# relay_dip_v03.net
KiCad netlist of a schematic drawn in EAGLE
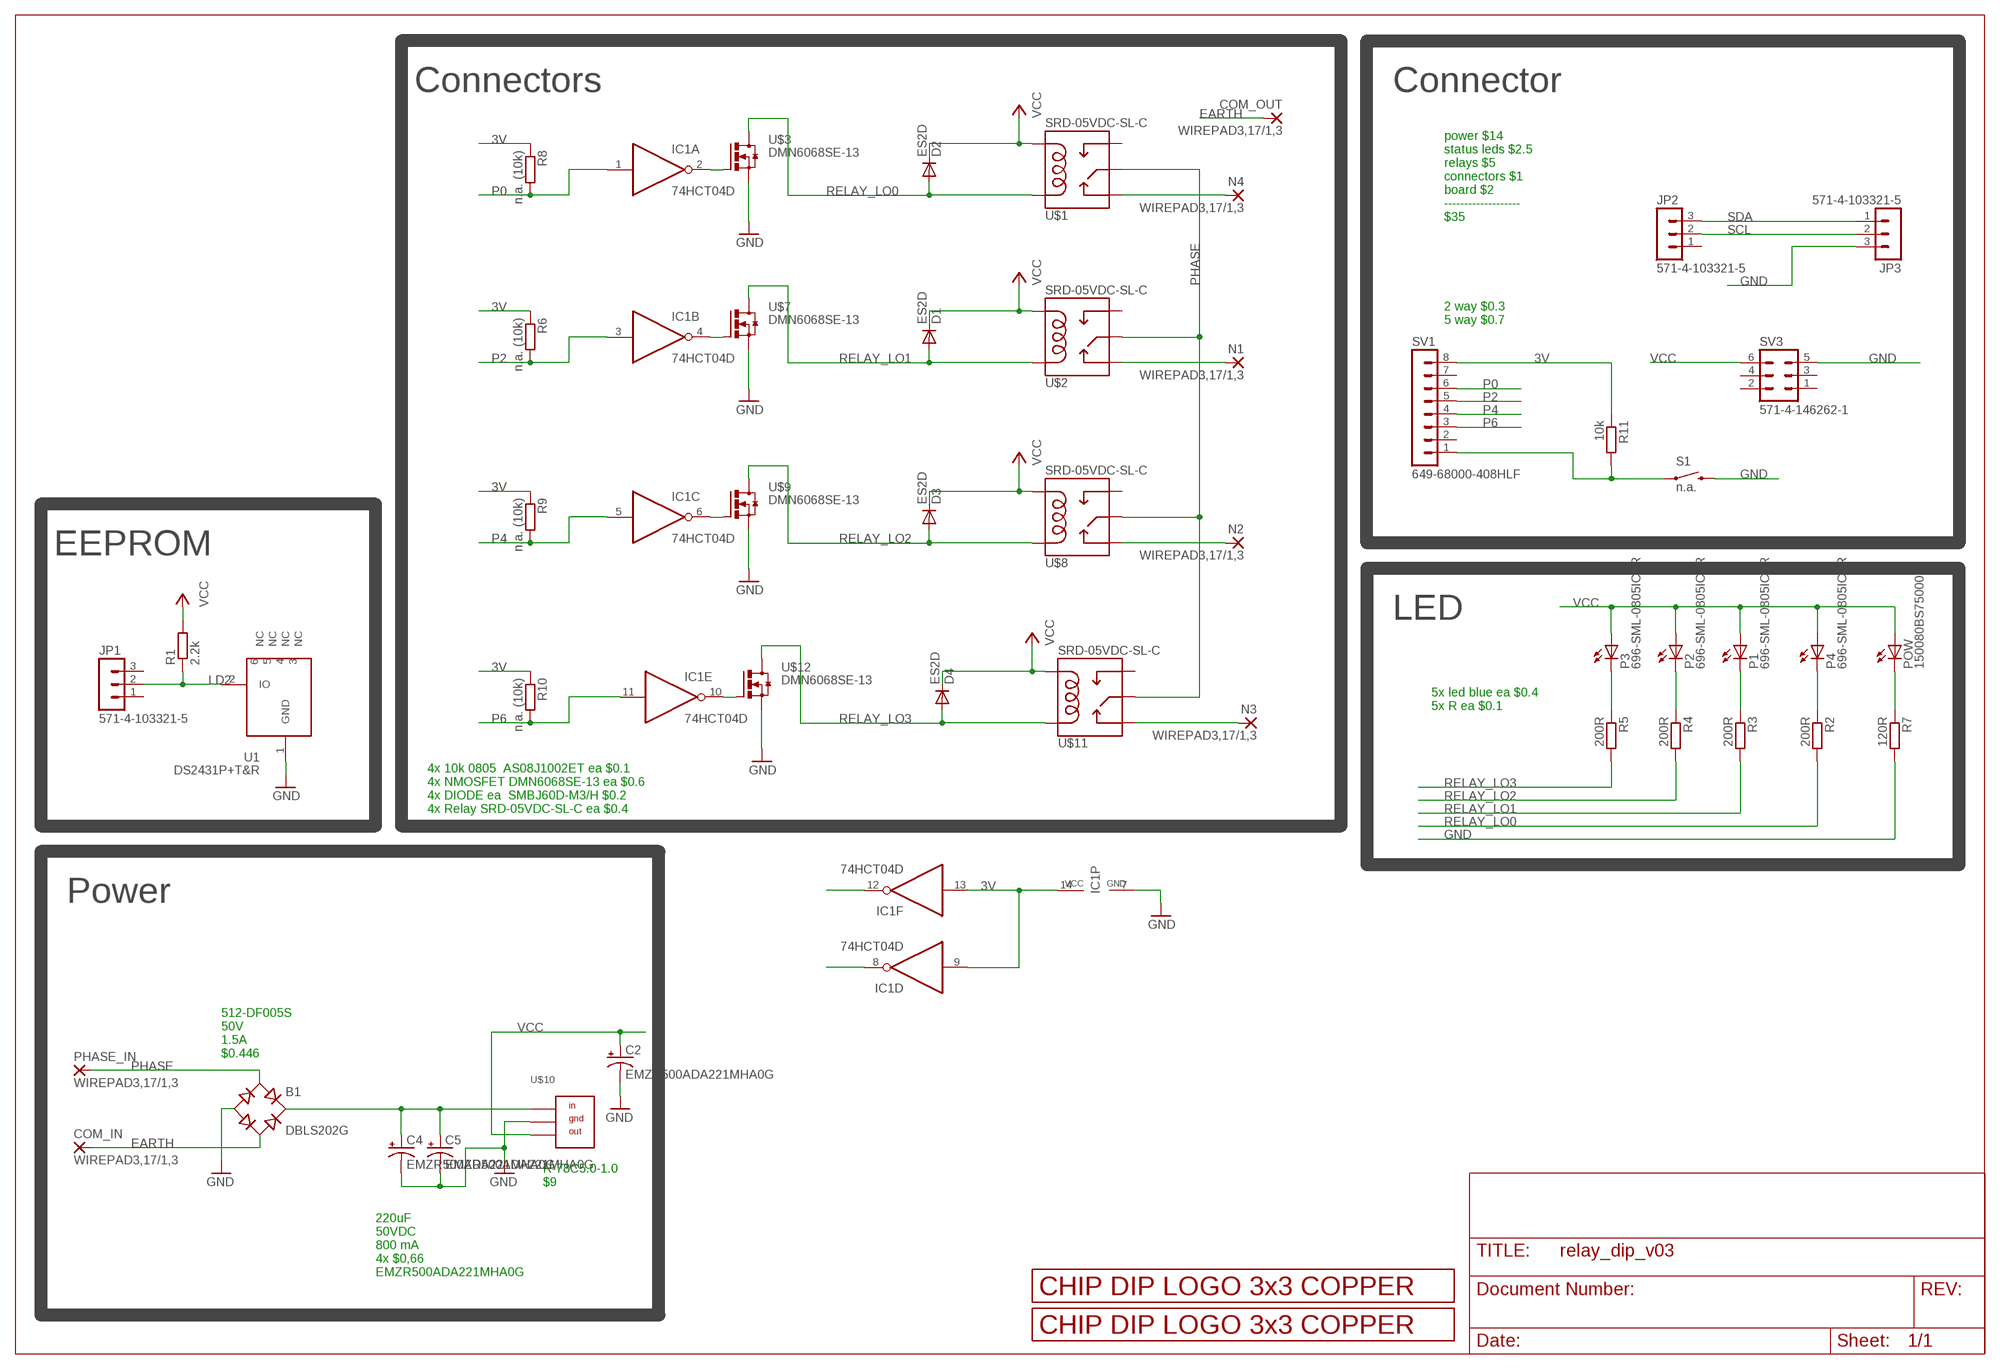
[diagram p0: schematic, sheet 1]

(export (version "E")
  (design (tool "Eeschema 10.0.6"))
  (components
    (comp (ref "B1")
      (value "DBLS202G")
      (footprint "eagle-import:DBS")
      (libsource (lib "eagle-import") (part "DB?GLS202"))
    )
    (comp (ref "C2")
      (value "EMZR500ADA221MHA0G")
      (footprint "eagle-import:150CLZ-0810")
      (libsource (lib "eagle-import") (part "CPOL-US150CLZ-0810"))
    )
    (comp (ref "C4")
      (value "EMZR500ADA221MHA0G")
      (footprint "eagle-import:150CLZ-0810")
      (libsource (lib "eagle-import") (part "CPOL-US150CLZ-0810"))
    )
    (comp (ref "C5")
      (value "EMZR500ADA221MHA0G")
      (footprint "eagle-import:150CLZ-0810")
      (libsource (lib "eagle-import") (part "CPOL-US150CLZ-0810"))
    )
    (comp (ref "COM_IN")
      (value "WIREPAD3,17/1,3")
      (footprint "eagle-import:3,17_1,3")
      (libsource (lib "eagle-import") (part "WIREPAD3,17/1,3"))
    )
    (comp (ref "COM_OUT")
      (value "WIREPAD3,17/1,3")
      (footprint "eagle-import:3,17_1,3")
      (libsource (lib "eagle-import") (part "WIREPAD3,17/1,3"))
    )
    (comp (ref "D1")
      (value "ES2D")
      (footprint "eagle-import:SMB")
      (libsource (lib "eagle-import") (part "DIODE-SMB"))
    )
    (comp (ref "D2")
      (value "ES2D")
      (footprint "eagle-import:SMB")
      (libsource (lib "eagle-import") (part "DIODE-SMB"))
    )
    (comp (ref "D3")
      (value "ES2D")
      (footprint "eagle-import:SMB")
      (libsource (lib "eagle-import") (part "DIODE-SMB"))
    )
    (comp (ref "D4")
      (value "ES2D")
      (footprint "eagle-import:SMB")
      (libsource (lib "eagle-import") (part "DIODE-SMB"))
    )
    (comp (ref "IC1")
      (value "74HCT04D")
      (footprint "eagle-import:SO14")
      (libsource (lib "eagle-import") (part "7404DHCT"))
    )
    (comp (ref "JP1")
      (value "571-4-103321-5")
      (footprint "eagle-import:MA03-1")
      (libsource (lib "eagle-import") (part "MA03-1"))
    )
    (comp (ref "JP2")
      (value "571-4-103321-5")
      (footprint "eagle-import:MA03-1")
      (libsource (lib "eagle-import") (part "MA03-1"))
    )
    (comp (ref "JP3")
      (value "571-4-103321-5")
      (footprint "eagle-import:MA03-1")
      (libsource (lib "eagle-import") (part "MA03-1"))
    )
    (comp (ref "N1")
      (value "WIREPAD3,17/1,3")
      (footprint "eagle-import:3,17_1,3")
      (libsource (lib "eagle-import") (part "WIREPAD3,17/1,3"))
    )
    (comp (ref "N2")
      (value "WIREPAD3,17/1,3")
      (footprint "eagle-import:3,17_1,3")
      (libsource (lib "eagle-import") (part "WIREPAD3,17/1,3"))
    )
    (comp (ref "N3")
      (value "WIREPAD3,17/1,3")
      (footprint "eagle-import:3,17_1,3")
      (libsource (lib "eagle-import") (part "WIREPAD3,17/1,3"))
    )
    (comp (ref "N4")
      (value "WIREPAD3,17/1,3")
      (footprint "eagle-import:3,17_1,3")
      (libsource (lib "eagle-import") (part "WIREPAD3,17/1,3"))
    )
    (comp (ref "P1")
      (value "696-SML-0805ICTR")
      (footprint "eagle-import:CHIP-LED0805")
      (libsource (lib "eagle-import") (part "LEDCHIP-LED0805"))
    )
    (comp (ref "P2")
      (value "696-SML-0805ICTR")
      (footprint "eagle-import:CHIP-LED0805")
      (libsource (lib "eagle-import") (part "LEDCHIP-LED0805"))
    )
    (comp (ref "P3")
      (value "696-SML-0805ICTR")
      (footprint "eagle-import:CHIP-LED0805")
      (libsource (lib "eagle-import") (part "LEDCHIP-LED0805"))
    )
    (comp (ref "P4")
      (value "696-SML-0805ICTR")
      (footprint "eagle-import:CHIP-LED0805")
      (libsource (lib "eagle-import") (part "LEDCHIP-LED0805"))
    )
    (comp (ref "PHASE_IN")
      (value "WIREPAD3,17/1,3")
      (footprint "eagle-import:3,17_1,3")
      (libsource (lib "eagle-import") (part "WIREPAD3,17/1,3"))
    )
    (comp (ref "POW")
      (value "150080BS75000")
      (footprint "eagle-import:CHIP-LED0805")
      (libsource (lib "eagle-import") (part "LEDCHIP-LED0805"))
    )
    (comp (ref "R1")
      (value "2.2k")
      (footprint "eagle-import:R0805")
      (libsource (lib "eagle-import") (part "R-EU_R0805"))
    )
    (comp (ref "R2")
      (value "200R")
      (footprint "eagle-import:R0805")
      (libsource (lib "eagle-import") (part "R-EU_R0805"))
    )
    (comp (ref "R3")
      (value "200R")
      (footprint "eagle-import:R0805")
      (libsource (lib "eagle-import") (part "R-EU_R0805"))
    )
    (comp (ref "R4")
      (value "200R")
      (footprint "eagle-import:R0805")
      (libsource (lib "eagle-import") (part "R-EU_R0805"))
    )
    (comp (ref "R5")
      (value "200R")
      (footprint "eagle-import:R0805")
      (libsource (lib "eagle-import") (part "R-EU_R0805"))
    )
    (comp (ref "R6")
      (value "n.a. (10k)")
      (footprint "eagle-import:R0805")
      (libsource (lib "eagle-import") (part "R-EU_R0805"))
    )
    (comp (ref "R7")
      (value "120R")
      (footprint "eagle-import:R0805")
      (libsource (lib "eagle-import") (part "R-EU_R0805"))
    )
    (comp (ref "R8")
      (value "n.a. (10k)")
      (footprint "eagle-import:R0805")
      (libsource (lib "eagle-import") (part "R-EU_R0805"))
    )
    (comp (ref "R9")
      (value "n.a. (10k)")
      (footprint "eagle-import:R0805")
      (libsource (lib "eagle-import") (part "R-EU_R0805"))
    )
    (comp (ref "R10")
      (value "n.a. (10k)")
      (footprint "eagle-import:R0805")
      (libsource (lib "eagle-import") (part "R-EU_R0805"))
    )
    (comp (ref "R11")
      (value "10k")
      (footprint "eagle-import:R0805")
      (libsource (lib "eagle-import") (part "R-EU_R0805"))
    )
    (comp (ref "S1")
      (value "n.a.")
      (footprint "eagle-import:TACTILE-SWITCH-SMD")
      (libsource (lib "eagle-import") (part "SWITCH-MOMENTARY-2SMD"))
    )
    (comp (ref "SV1")
      (value "649-68000-408HLF")
      (footprint "eagle-import:MA08-1")
      (libsource (lib "eagle-import") (part "MA08-1"))
    )
    (comp (ref "SV3")
      (value "571-4-146262-1")
      (footprint "eagle-import:MA03-2")
      (libsource (lib "eagle-import") (part "MA03-2"))
    )
    (comp (ref "U$1")
      (value "SRD-05VDC-SL-C")
      (footprint "eagle-import:SRD-05VDC-SL-C")
      (libsource (lib "eagle-import") (part "RELAYPTH"))
    )
    (comp (ref "U$2")
      (value "SRD-05VDC-SL-C")
      (footprint "eagle-import:SRD-05VDC-SL-C")
      (libsource (lib "eagle-import") (part "RELAYPTH"))
    )
    (comp (ref "U$3")
      (value "DMN6068SE-13")
      (footprint "eagle-import:SOT223")
      (libsource (lib "eagle-import") (part "NMOSFET_SMD_223"))
    )
    (comp (ref "U$4")
      (value "LOGO_3X3_COPPER")
      (footprint "eagle-import:LOGO_3X3_COPPER")
      (libsource (lib "eagle-import") (part "LOGO_3X3_COPPER"))
    )
    (comp (ref "U$6")
      (value "LOGO_3X3_COPPER")
      (footprint "eagle-import:LOGO_3X3_COPPER")
      (libsource (lib "eagle-import") (part "LOGO_3X3_COPPER"))
    )
    (comp (ref "U$7")
      (value "DMN6068SE-13")
      (footprint "eagle-import:SOT223")
      (libsource (lib "eagle-import") (part "NMOSFET_SMD_223"))
    )
    (comp (ref "U$8")
      (value "SRD-05VDC-SL-C")
      (footprint "eagle-import:SRD-05VDC-SL-C")
      (libsource (lib "eagle-import") (part "RELAYPTH"))
    )
    (comp (ref "U$9")
      (value "DMN6068SE-13")
      (footprint "eagle-import:SOT223")
      (libsource (lib "eagle-import") (part "NMOSFET_SMD_223"))
    )
    (comp (ref "U$10")
      (value "R-7805-1.0")
      (footprint "eagle-import:SIP3")
      (libsource (lib "eagle-import") (part "R-7805-1.0"))
    )
    (comp (ref "U$11")
      (value "SRD-05VDC-SL-C")
      (footprint "eagle-import:SRD-05VDC-SL-C")
      (libsource (lib "eagle-import") (part "RELAYPTH"))
    )
    (comp (ref "U$12")
      (value "DMN6068SE-13")
      (footprint "eagle-import:SOT223")
      (libsource (lib "eagle-import") (part "NMOSFET_SMD_223"))
    )
    (comp (ref "U1")
      (value "DS2431P+T&R")
      (footprint "eagle-import:TSOC6")
      (fields (field (name "MFG") "DIGIKEY"))
      (libsource (lib "eagle-import") (part "DS2431P"))
    )
  )
  (nets
    (net (code "1") (name "/3V") (class "Default")
      (node (ref "IC1") (pin "13") (pinfunction "I_13") (pintype "input"))
      (node (ref "IC1") (pin "14") (pinfunction "VCC_14") (pintype "power_in"))
      (node (ref "IC1") (pin "9") (pinfunction "I_9") (pintype "input"))
      (node (ref "R10") (pin "1") (pinfunction "1_1") (pintype "passive"))
      (node (ref "R11") (pin "1") (pinfunction "1_1") (pintype "passive"))
      (node (ref "R6") (pin "1") (pinfunction "1_1") (pintype "passive"))
      (node (ref "R8") (pin "1") (pinfunction "1_1") (pintype "passive"))
      (node (ref "R9") (pin "1") (pinfunction "1_1") (pintype "passive"))
      (node (ref "SV1") (pin "8") (pinfunction "8_8") (pintype "passive"))
    )
    (net (code "2") (name "/EARTH") (class "Default")
      (node (ref "B1") (pin "AC2") (pinfunction "AC2_AC2") (pintype "passive"))
      (node (ref "COM_IN") (pin "1") (pinfunction "P_1") (pintype "passive"))
      (node (ref "COM_OUT") (pin "1") (pinfunction "P_1") (pintype "passive"))
    )
    (net (code "3") (name "/LD2") (class "Default")
      (node (ref "JP1") (pin "2") (pinfunction "2_2") (pintype "passive"))
      (node (ref "R1") (pin "1") (pinfunction "1_1") (pintype "passive"))
      (node (ref "U1") (pin "2") (pinfunction "IO_2") (pintype "bidirectional"))
    )
    (net (code "4") (name "/P0") (class "Default")
      (node (ref "IC1") (pin "1") (pinfunction "I_1") (pintype "input"))
      (node (ref "R8") (pin "2") (pinfunction "2_2") (pintype "passive"))
      (node (ref "SV1") (pin "6") (pinfunction "6_6") (pintype "passive"))
    )
    (net (code "5") (name "/P2") (class "Default")
      (node (ref "IC1") (pin "3") (pinfunction "I_3") (pintype "input"))
      (node (ref "R6") (pin "2") (pinfunction "2_2") (pintype "passive"))
      (node (ref "SV1") (pin "5") (pinfunction "5_5") (pintype "passive"))
    )
    (net (code "6") (name "/P4") (class "Default")
      (node (ref "IC1") (pin "5") (pinfunction "I_5") (pintype "input"))
      (node (ref "R9") (pin "2") (pinfunction "2_2") (pintype "passive"))
      (node (ref "SV1") (pin "4") (pinfunction "4_4") (pintype "passive"))
    )
    (net (code "7") (name "/P6") (class "Default")
      (node (ref "IC1") (pin "11") (pinfunction "I_11") (pintype "input"))
      (node (ref "R10") (pin "2") (pinfunction "2_2") (pintype "passive"))
      (node (ref "SV1") (pin "3") (pinfunction "3_3") (pintype "passive"))
    )
    (net (code "8") (name "/PHASE") (class "Default")
      (node (ref "B1") (pin "AC1") (pinfunction "AC1_AC1") (pintype "passive"))
      (node (ref "PHASE_IN") (pin "1") (pinfunction "P_1") (pintype "passive"))
      (node (ref "U$1") (pin "SWCOMMON") (pinfunction "SWCOMMON_SWCOMMON") (pintype "bidirectional"))
      (node (ref "U$11") (pin "SWCOMMON") (pinfunction "SWCOMMON_SWCOMMON") (pintype "bidirectional"))
      (node (ref "U$2") (pin "SWCOMMON") (pinfunction "SWCOMMON_SWCOMMON") (pintype "bidirectional"))
      (node (ref "U$8") (pin "SWCOMMON") (pinfunction "SWCOMMON_SWCOMMON") (pintype "bidirectional"))
    )
    (net (code "9") (name "/RELAY_LO0") (class "Default")
      (node (ref "D2") (pin "A") (pinfunction "A_A") (pintype "passive"))
      (node (ref "R2") (pin "2") (pinfunction "2_2") (pintype "passive"))
      (node (ref "U$1") (pin "COIL1") (pinfunction "COIL1_COIL1") (pintype "bidirectional"))
      (node (ref "U$3") (pin "2") (pinfunction "D_2") (pintype "passive"))
      (node (ref "U$3") (pin "4") (pinfunction "D_4") (pintype "passive"))
    )
    (net (code "10") (name "/RELAY_LO1") (class "Default")
      (node (ref "D1") (pin "A") (pinfunction "A_A") (pintype "passive"))
      (node (ref "R3") (pin "2") (pinfunction "2_2") (pintype "passive"))
      (node (ref "U$2") (pin "COIL1") (pinfunction "COIL1_COIL1") (pintype "bidirectional"))
      (node (ref "U$7") (pin "2") (pinfunction "D_2") (pintype "passive"))
      (node (ref "U$7") (pin "4") (pinfunction "D_4") (pintype "passive"))
    )
    (net (code "11") (name "/RELAY_LO2") (class "Default")
      (node (ref "D3") (pin "A") (pinfunction "A_A") (pintype "passive"))
      (node (ref "R4") (pin "2") (pinfunction "2_2") (pintype "passive"))
      (node (ref "U$8") (pin "COIL1") (pinfunction "COIL1_COIL1") (pintype "bidirectional"))
      (node (ref "U$9") (pin "2") (pinfunction "D_2") (pintype "passive"))
      (node (ref "U$9") (pin "4") (pinfunction "D_4") (pintype "passive"))
    )
    (net (code "12") (name "/RELAY_LO3") (class "Default")
      (node (ref "D4") (pin "A") (pinfunction "A_A") (pintype "passive"))
      (node (ref "R5") (pin "2") (pinfunction "2_2") (pintype "passive"))
      (node (ref "U$11") (pin "COIL1") (pinfunction "COIL1_COIL1") (pintype "bidirectional"))
      (node (ref "U$12") (pin "2") (pinfunction "D_2") (pintype "passive"))
      (node (ref "U$12") (pin "4") (pinfunction "D_4") (pintype "passive"))
    )
    (net (code "13") (name "/SCL") (class "Default")
      (node (ref "JP2") (pin "2") (pinfunction "2_2") (pintype "passive"))
      (node (ref "JP3") (pin "2") (pinfunction "2_2") (pintype "passive"))
    )
    (net (code "14") (name "/SDA") (class "Default")
      (node (ref "JP2") (pin "3") (pinfunction "3_3") (pintype "passive"))
      (node (ref "JP3") (pin "1") (pinfunction "1_1") (pintype "passive"))
    )
    (net (code "15") (name "GND") (class "Default")
      (node (ref "B1") (pin "-") (pinfunction "-_-") (pintype "passive"))
      (node (ref "C2") (pin "-") (pinfunction "-_-") (pintype "passive"))
      (node (ref "C4") (pin "-") (pinfunction "-_-") (pintype "passive"))
      (node (ref "C5") (pin "-") (pinfunction "-_-") (pintype "passive"))
      (node (ref "IC1") (pin "7") (pinfunction "GND_7") (pintype "power_in"))
      (node (ref "JP3") (pin "3") (pinfunction "3_3") (pintype "passive"))
      (node (ref "R7") (pin "2") (pinfunction "2_2") (pintype "passive"))
      (node (ref "S1") (pin "3") (pinfunction "2_3") (pintype "passive"))
      (node (ref "SV3") (pin "5") (pinfunction "5_5") (pintype "passive"))
      (node (ref "U$10") (pin "GND") (pinfunction "GND_GND") (pintype "bidirectional"))
      (node (ref "U$12") (pin "3") (pinfunction "S_3") (pintype "passive"))
      (node (ref "U$3") (pin "3") (pinfunction "S_3") (pintype "passive"))
      (node (ref "U$7") (pin "3") (pinfunction "S_3") (pintype "passive"))
      (node (ref "U$9") (pin "3") (pinfunction "S_3") (pintype "passive"))
      (node (ref "U1") (pin "1") (pinfunction "GND_1") (pintype "bidirectional"))
    )
    (net (code "16") (name "Net-(B1-Pad+)") (class "Default")
      (node (ref "B1") (pin "+") (pinfunction "+_+") (pintype "passive"))
      (node (ref "C4") (pin "+") (pinfunction "+_+") (pintype "passive"))
      (node (ref "C5") (pin "+") (pinfunction "+_+") (pintype "passive"))
      (node (ref "U$10") (pin "IN") (pinfunction "IN_IN") (pintype "bidirectional"))
    )
    (net (code "17") (name "Net-(IC1A-O)") (class "Default")
      (node (ref "IC1") (pin "2") (pinfunction "O_2") (pintype "output"))
      (node (ref "U$3") (pin "1") (pinfunction "G_1") (pintype "passive"))
    )
    (net (code "18") (name "Net-(IC1B-O)") (class "Default")
      (node (ref "IC1") (pin "4") (pinfunction "O_4") (pintype "output"))
      (node (ref "U$7") (pin "1") (pinfunction "G_1") (pintype "passive"))
    )
    (net (code "19") (name "Net-(IC1C-O)") (class "Default")
      (node (ref "IC1") (pin "6") (pinfunction "O_6") (pintype "output"))
      (node (ref "U$9") (pin "1") (pinfunction "G_1") (pintype "passive"))
    )
    (net (code "20") (name "Net-(IC1E-O)") (class "Default")
      (node (ref "IC1") (pin "10") (pinfunction "O_10") (pintype "output"))
      (node (ref "U$12") (pin "1") (pinfunction "G_1") (pintype "passive"))
    )
    (net (code "21") (name "Net-(N1-P)") (class "Default")
      (node (ref "N1") (pin "1") (pinfunction "P_1") (pintype "passive"))
      (node (ref "U$2") (pin "SWCLOSED") (pinfunction "SWCLOSE_SWCLOSED") (pintype "bidirectional"))
    )
    (net (code "22") (name "Net-(N2-P)") (class "Default")
      (node (ref "N2") (pin "1") (pinfunction "P_1") (pintype "passive"))
      (node (ref "U$8") (pin "SWCLOSED") (pinfunction "SWCLOSE_SWCLOSED") (pintype "bidirectional"))
    )
    (net (code "23") (name "Net-(N3-P)") (class "Default")
      (node (ref "N3") (pin "1") (pinfunction "P_1") (pintype "passive"))
      (node (ref "U$11") (pin "SWCLOSED") (pinfunction "SWCLOSE_SWCLOSED") (pintype "bidirectional"))
    )
    (net (code "24") (name "Net-(N4-P)") (class "Default")
      (node (ref "N4") (pin "1") (pinfunction "P_1") (pintype "passive"))
      (node (ref "U$1") (pin "SWCLOSED") (pinfunction "SWCLOSE_SWCLOSED") (pintype "bidirectional"))
    )
    (net (code "25") (name "Net-(P1-PadC)") (class "Default")
      (node (ref "P1") (pin "C") (pinfunction "C_C") (pintype "passive"))
      (node (ref "R3") (pin "1") (pinfunction "1_1") (pintype "passive"))
    )
    (net (code "26") (name "Net-(P2-PadC)") (class "Default")
      (node (ref "P2") (pin "C") (pinfunction "C_C") (pintype "passive"))
      (node (ref "R4") (pin "1") (pinfunction "1_1") (pintype "passive"))
    )
    (net (code "27") (name "Net-(P3-PadC)") (class "Default")
      (node (ref "P3") (pin "C") (pinfunction "C_C") (pintype "passive"))
      (node (ref "R5") (pin "1") (pinfunction "1_1") (pintype "passive"))
    )
    (net (code "28") (name "Net-(P4-PadC)") (class "Default")
      (node (ref "P4") (pin "C") (pinfunction "C_C") (pintype "passive"))
      (node (ref "R2") (pin "1") (pinfunction "1_1") (pintype "passive"))
    )
    (net (code "29") (name "Net-(POW-PadC)") (class "Default")
      (node (ref "POW") (pin "C") (pinfunction "C_C") (pintype "passive"))
      (node (ref "R7") (pin "1") (pinfunction "1_1") (pintype "passive"))
    )
    (net (code "30") (name "Net-(R11-Pad2)") (class "Default")
      (node (ref "R11") (pin "2") (pinfunction "2_2") (pintype "passive"))
      (node (ref "S1") (pin "1") (pinfunction "1_1") (pintype "passive"))
      (node (ref "SV1") (pin "1") (pinfunction "1_1") (pintype "passive"))
    )
    (net (code "31") (name "VCC") (class "Default")
      (node (ref "C2") (pin "+") (pinfunction "+_+") (pintype "passive"))
      (node (ref "D1") (pin "C") (pinfunction "C_C") (pintype "passive"))
      (node (ref "D2") (pin "C") (pinfunction "C_C") (pintype "passive"))
      (node (ref "D3") (pin "C") (pinfunction "C_C") (pintype "passive"))
      (node (ref "D4") (pin "C") (pinfunction "C_C") (pintype "passive"))
      (node (ref "P1") (pin "A") (pinfunction "A_A") (pintype "passive"))
      (node (ref "P2") (pin "A") (pinfunction "A_A") (pintype "passive"))
      (node (ref "P3") (pin "A") (pinfunction "A_A") (pintype "passive"))
      (node (ref "P4") (pin "A") (pinfunction "A_A") (pintype "passive"))
      (node (ref "POW") (pin "A") (pinfunction "A_A") (pintype "passive"))
      (node (ref "R1") (pin "2") (pinfunction "2_2") (pintype "passive"))
      (node (ref "SV3") (pin "6") (pinfunction "6_6") (pintype "passive"))
      (node (ref "U$1") (pin "COIL0") (pinfunction "COIL0_COIL0") (pintype "bidirectional"))
      (node (ref "U$10") (pin "OUT") (pinfunction "OUT_OUT") (pintype "bidirectional"))
      (node (ref "U$11") (pin "COIL0") (pinfunction "COIL0_COIL0") (pintype "bidirectional"))
      (node (ref "U$2") (pin "COIL0") (pinfunction "COIL0_COIL0") (pintype "bidirectional"))
      (node (ref "U$8") (pin "COIL0") (pinfunction "COIL0_COIL0") (pintype "bidirectional"))
    )
    (net (code "32") (name "unconnected-(IC1D-O-Pad8)") (class "Default")
      (node (ref "IC1") (pin "8") (pinfunction "O_8") (pintype "output"))
    )
    (net (code "33") (name "unconnected-(IC1F-O-Pad12)") (class "Default")
      (node (ref "IC1") (pin "12") (pinfunction "O_12") (pintype "output"))
    )
    (net (code "34") (name "unconnected-(JP1-Pad1)") (class "Default")
      (node (ref "JP1") (pin "1") (pinfunction "1_1") (pintype "passive"))
    )
    (net (code "35") (name "unconnected-(JP1-Pad3)") (class "Default")
      (node (ref "JP1") (pin "3") (pinfunction "3_3") (pintype "passive"))
    )
    (net (code "36") (name "unconnected-(JP2-Pad1)") (class "Default")
      (node (ref "JP2") (pin "1") (pinfunction "1_1") (pintype "passive"))
    )
    (net (code "37") (name "unconnected-(SV1-Pad2)") (class "Default")
      (node (ref "SV1") (pin "2") (pinfunction "2_2") (pintype "passive"))
    )
    (net (code "38") (name "unconnected-(SV1-Pad7)") (class "Default")
      (node (ref "SV1") (pin "7") (pinfunction "7_7") (pintype "passive"))
    )
    (net (code "39") (name "unconnected-(SV3-Pad1)") (class "Default")
      (node (ref "SV3") (pin "1") (pinfunction "1_1") (pintype "passive"))
    )
    (net (code "40") (name "unconnected-(SV3-Pad2)") (class "Default")
      (node (ref "SV3") (pin "2") (pinfunction "2_2") (pintype "passive"))
    )
    (net (code "41") (name "unconnected-(SV3-Pad3)") (class "Default")
      (node (ref "SV3") (pin "3") (pinfunction "3_3") (pintype "passive"))
    )
    (net (code "42") (name "unconnected-(SV3-Pad4)") (class "Default")
      (node (ref "SV3") (pin "4") (pinfunction "4_4") (pintype "passive"))
    )
    (net (code "43") (name "unconnected-(U$1-PadSWOPEN)") (class "Default")
      (node (ref "U$1") (pin "SWOPEN") (pinfunction "SWOPEN_SWOPEN") (pintype "bidirectional"))
    )
    (net (code "44") (name "unconnected-(U$2-PadSWOPEN)") (class "Default")
      (node (ref "U$2") (pin "SWOPEN") (pinfunction "SWOPEN_SWOPEN") (pintype "bidirectional"))
    )
    (net (code "45") (name "unconnected-(U$8-PadSWOPEN)") (class "Default")
      (node (ref "U$8") (pin "SWOPEN") (pinfunction "SWOPEN_SWOPEN") (pintype "bidirectional"))
    )
    (net (code "46") (name "unconnected-(U$11-PadSWOPEN)") (class "Default")
      (node (ref "U$11") (pin "SWOPEN") (pinfunction "SWOPEN_SWOPEN") (pintype "bidirectional"))
    )
    (net (code "47") (name "unconnected-(U1-NC-Pad3)") (class "Default")
      (node (ref "U1") (pin "3") (pinfunction "NC_3") (pintype "bidirectional"))
    )
    (net (code "48") (name "unconnected-(U1-NC-Pad4)") (class "Default")
      (node (ref "U1") (pin "4") (pinfunction "NC_4") (pintype "bidirectional"))
    )
    (net (code "49") (name "unconnected-(U1-NC-Pad5)") (class "Default")
      (node (ref "U1") (pin "5") (pinfunction "NC_5") (pintype "bidirectional"))
    )
    (net (code "50") (name "unconnected-(U1-NC-Pad6)") (class "Default")
      (node (ref "U1") (pin "6") (pinfunction "NC_6") (pintype "bidirectional"))
    )
  )
)
